# 6_CODEC.net
KiCad netlist of a schematic drawn in Altium Designer
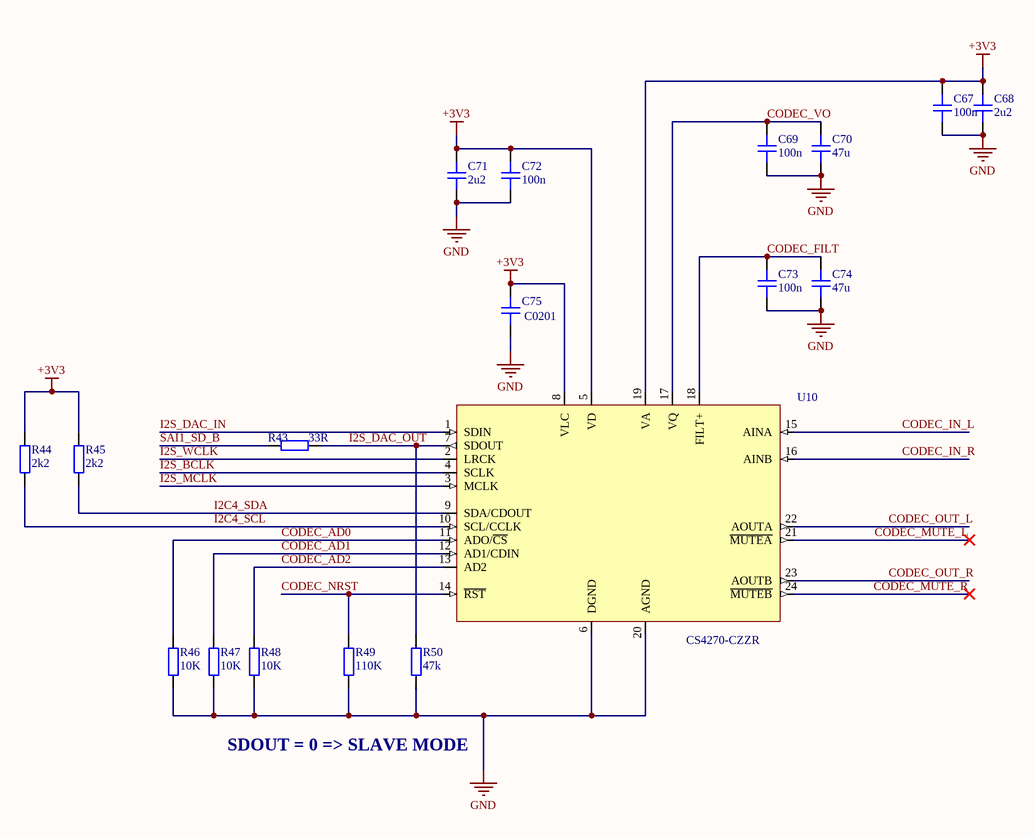
[diagram p0: 6_CODEC.SchDoc]

(export (version "E")
  (design (tool "Eeschema 10.0.6"))
  (components
    (comp (ref "C67")
      (value "100n")
      (footprint "CAP_0201")
      (description "Capacitor SMD 0201")
      (libsource (lib "Schematic-Lib-PhilsLab") (part "CAP_0201"))
    )
    (comp (ref "C68")
      (value "2u2")
      (footprint "CAP_0201")
      (description "Capacitor SMD 0201")
      (libsource (lib "Schematic-Lib-PhilsLab") (part "CAP_0201"))
    )
    (comp (ref "C69")
      (value "100n")
      (footprint "CAP_0201")
      (description "Capacitor SMD 0201")
      (libsource (lib "Schematic-Lib-PhilsLab") (part "CAP_0201"))
    )
    (comp (ref "C70")
      (value "47u")
      (footprint "CAP_0201")
      (description "Capacitor SMD 0201")
      (libsource (lib "Schematic-Lib-PhilsLab") (part "CAP_0201"))
    )
    (comp (ref "C71")
      (value "2u2")
      (footprint "CAP_0201")
      (description "Capacitor SMD 0201")
      (libsource (lib "Schematic-Lib-PhilsLab") (part "CAP_0201"))
    )
    (comp (ref "C72")
      (value "100n")
      (footprint "CAP_0201")
      (description "Capacitor SMD 0201")
      (libsource (lib "Schematic-Lib-PhilsLab") (part "CAP_0201"))
    )
    (comp (ref "C73")
      (value "100n")
      (footprint "CAP_0201")
      (description "Capacitor SMD 0201")
      (libsource (lib "Schematic-Lib-PhilsLab") (part "CAP_0201"))
    )
    (comp (ref "C74")
      (value "47u")
      (footprint "CAP_0201")
      (description "Capacitor SMD 0201")
      (libsource (lib "Schematic-Lib-PhilsLab") (part "CAP_0201"))
    )
    (comp (ref "C75")
      (value "C0201")
      (footprint "CAP_0201")
      (description "Capacitor SMD 0201")
      (libsource (lib "Schematic-Lib-PhilsLab") (part "CAP_0201"))
    )
    (comp (ref "R43")
      (value "33R")
      (footprint "RES_0402")
      (description "Resistor SMD 0402")
      (libsource (lib "Schematic-Lib-PhilsLab") (part "RES_0402"))
    )
    (comp (ref "R44")
      (value "2k2")
      (footprint "RES_0402")
      (description "Resistor SMD 0402")
      (libsource (lib "Schematic-Lib-PhilsLab") (part "RES_0402"))
    )
    (comp (ref "R45")
      (value "2k2")
      (footprint "RES_0402")
      (description "Resistor SMD 0402")
      (libsource (lib "Schematic-Lib-PhilsLab") (part "RES_0402"))
    )
    (comp (ref "R46")
      (value "10K")
      (footprint "RES_0402")
      (description "Resistor SMD 0402")
      (libsource (lib "Schematic-Lib-PhilsLab") (part "RES_0402"))
    )
    (comp (ref "R47")
      (value "10K")
      (footprint "RES_0402")
      (description "Resistor SMD 0402")
      (libsource (lib "Schematic-Lib-PhilsLab") (part "RES_0402"))
    )
    (comp (ref "R48")
      (value "10K")
      (footprint "RES_0402")
      (description "Resistor SMD 0402")
      (libsource (lib "Schematic-Lib-PhilsLab") (part "RES_0402"))
    )
    (comp (ref "R49")
      (value "110K")
      (footprint "RES_0402")
      (description "Resistor SMD 0402")
      (libsource (lib "Schematic-Lib-PhilsLab") (part "RES_0402"))
    )
    (comp (ref "R50")
      (value "47k")
      (footprint "RES_0402")
      (description "Resistor SMD 0402")
      (libsource (lib "Schematic-Lib-PhilsLab") (part "RES_0402"))
    )
    (comp (ref "U10")
      (value "CS4270-CZZR")
      (footprint "TSSOP-24")
      (description "24-Bit 192kHz Stereo Audio Codec TSSOP-24")
      (fields (field (name "MANUFACTURER") "Cirrus Logic"))
      (libsource (lib "Schematic-Lib-PhilsLab") (part "CS4270-CZZR"))
    )
  )
  (nets
    (net (code "1") (name "+3V3") (class "Default")
      (node (ref "C67") (pin "2") (pinfunction "2_2") (pintype "passive"))
      (node (ref "C68") (pin "2") (pinfunction "2_2") (pintype "passive"))
      (node (ref "C71") (pin "2") (pinfunction "2_2") (pintype "passive"))
      (node (ref "C72") (pin "2") (pinfunction "2_2") (pintype "passive"))
      (node (ref "C75") (pin "2") (pinfunction "2_2") (pintype "passive"))
      (node (ref "R44") (pin "1") (pinfunction "1_1") (pintype "passive"))
      (node (ref "R45") (pin "1") (pinfunction "1_1") (pintype "passive"))
      (node (ref "U10") (pin "19") (pinfunction "VA_19") (pintype "power_in"))
      (node (ref "U10") (pin "5") (pinfunction "VD_5") (pintype "power_in"))
      (node (ref "U10") (pin "8") (pinfunction "VLC_8") (pintype "power_in"))
    )
    (net (code "2") (name "/CODEC_AD0") (class "Default")
      (node (ref "R46") (pin "2") (pinfunction "2_2") (pintype "passive"))
      (node (ref "U10") (pin "11") (pinfunction "ADO/~{CS}_11") (pintype "input"))
    )
    (net (code "3") (name "/CODEC_AD1") (class "Default")
      (node (ref "R47") (pin "2") (pinfunction "2_2") (pintype "passive"))
      (node (ref "U10") (pin "12") (pinfunction "AD1/CDIN_12") (pintype "input"))
    )
    (net (code "4") (name "/CODEC_AD2") (class "Default")
      (node (ref "R48") (pin "2") (pinfunction "2_2") (pintype "passive"))
      (node (ref "U10") (pin "13") (pinfunction "AD2_13") (pintype "passive"))
    )
    (net (code "5") (name "/CODEC_FILT") (class "Default")
      (node (ref "C73") (pin "2") (pinfunction "2_2") (pintype "passive"))
      (node (ref "C74") (pin "2") (pinfunction "2_2") (pintype "passive"))
      (node (ref "U10") (pin "18") (pinfunction "FILT+_18") (pintype "power_in"))
    )
    (net (code "6") (name "/CODEC_IN_L") (class "Default")
      (node (ref "U10") (pin "15") (pinfunction "AINA_15") (pintype "input"))
    )
    (net (code "7") (name "/CODEC_IN_R") (class "Default")
      (node (ref "U10") (pin "16") (pinfunction "AINB_16") (pintype "input"))
    )
    (net (code "8") (name "/CODEC_MUTE_L") (class "Default")
      (node (ref "U10") (pin "21") (pinfunction "~{MUTEA}_21") (pintype "output+no_connect"))
    )
    (net (code "9") (name "/CODEC_MUTE_R") (class "Default")
      (node (ref "U10") (pin "24") (pinfunction "~{MUTEB}_24") (pintype "output+no_connect"))
    )
    (net (code "10") (name "/CODEC_NRST") (class "Default")
      (node (ref "R49") (pin "2") (pinfunction "2_2") (pintype "passive"))
      (node (ref "U10") (pin "14") (pinfunction "~{RST}_14") (pintype "input"))
    )
    (net (code "11") (name "/CODEC_OUT_L") (class "Default")
      (node (ref "U10") (pin "22") (pinfunction "AOUTA_22") (pintype "output"))
    )
    (net (code "12") (name "/CODEC_OUT_R") (class "Default")
      (node (ref "U10") (pin "23") (pinfunction "AOUTB_23") (pintype "output"))
    )
    (net (code "13") (name "/CODEC_VO") (class "Default")
      (node (ref "C69") (pin "2") (pinfunction "2_2") (pintype "passive"))
      (node (ref "C70") (pin "2") (pinfunction "2_2") (pintype "passive"))
      (node (ref "U10") (pin "17") (pinfunction "VQ_17") (pintype "power_in"))
    )
    (net (code "14") (name "/I2C4_SCL") (class "Default")
      (node (ref "R44") (pin "2") (pinfunction "2_2") (pintype "passive"))
      (node (ref "U10") (pin "10") (pinfunction "SCL/CCLK_10") (pintype "input"))
    )
    (net (code "15") (name "/I2C4_SDA") (class "Default")
      (node (ref "R45") (pin "2") (pinfunction "2_2") (pintype "passive"))
      (node (ref "U10") (pin "9") (pinfunction "SDA/CDOUT_9") (pintype "bidirectional"))
    )
    (net (code "16") (name "/I2S_BCLK") (class "Default")
      (node (ref "U10") (pin "4") (pinfunction "SCLK_4") (pintype "bidirectional"))
    )
    (net (code "17") (name "/I2S_DAC_IN") (class "Default")
      (node (ref "U10") (pin "1") (pinfunction "SDIN_1") (pintype "input"))
    )
    (net (code "18") (name "/I2S_DAC_OUT") (class "Default")
      (node (ref "R43") (pin "1") (pinfunction "1_1") (pintype "passive"))
      (node (ref "R50") (pin "2") (pinfunction "2_2") (pintype "passive"))
      (node (ref "U10") (pin "7") (pinfunction "SDOUT_7") (pintype "output"))
    )
    (net (code "19") (name "/I2S_MCLK") (class "Default")
      (node (ref "U10") (pin "3") (pinfunction "MCLK_3") (pintype "input"))
    )
    (net (code "20") (name "/I2S_WCLK") (class "Default")
      (node (ref "U10") (pin "2") (pinfunction "LRCK_2") (pintype "bidirectional"))
    )
    (net (code "21") (name "/SAI1_SD_B") (class "Default")
      (node (ref "R43") (pin "2") (pinfunction "2_2") (pintype "passive"))
    )
    (net (code "22") (name "GND") (class "Default")
      (node (ref "C67") (pin "1") (pinfunction "1_1") (pintype "passive"))
      (node (ref "C68") (pin "1") (pinfunction "1_1") (pintype "passive"))
      (node (ref "C69") (pin "1") (pinfunction "1_1") (pintype "passive"))
      (node (ref "C70") (pin "1") (pinfunction "1_1") (pintype "passive"))
      (node (ref "C71") (pin "1") (pinfunction "1_1") (pintype "passive"))
      (node (ref "C72") (pin "1") (pinfunction "1_1") (pintype "passive"))
      (node (ref "C73") (pin "1") (pinfunction "1_1") (pintype "passive"))
      (node (ref "C74") (pin "1") (pinfunction "1_1") (pintype "passive"))
      (node (ref "C75") (pin "1") (pinfunction "1_1") (pintype "passive"))
      (node (ref "R46") (pin "1") (pinfunction "1_1") (pintype "passive"))
      (node (ref "R47") (pin "1") (pinfunction "1_1") (pintype "passive"))
      (node (ref "R48") (pin "1") (pinfunction "1_1") (pintype "passive"))
      (node (ref "R49") (pin "1") (pinfunction "1_1") (pintype "passive"))
      (node (ref "R50") (pin "1") (pinfunction "1_1") (pintype "passive"))
      (node (ref "U10") (pin "20") (pinfunction "AGND_20") (pintype "power_in"))
      (node (ref "U10") (pin "6") (pinfunction "DGND_6") (pintype "power_in"))
    )
  )
)
